# modular_pcb4.net
KiCad netlist of a schematic drawn in EAGLE
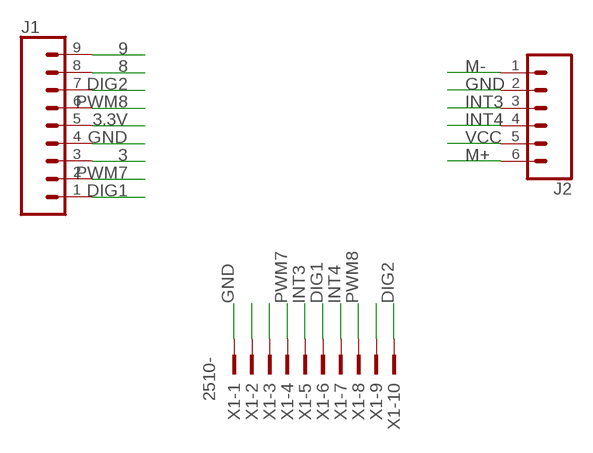
[diagram p0: schematic, sheet 1]

(export (version "E")
  (design (tool "Eeschema 10.0.6"))
  (components
    (comp (ref "J1")
      (value "CONN_09")
      (footprint "eagle-import:1X09")
      (libsource (lib "eagle-import") (part "CONN_09"))
    )
    (comp (ref "J2")
      (value "CONN_06FEMALE_LOCK")
      (footprint "eagle-import:1X06_FEMALE_LOCK.010")
      (libsource (lib "eagle-import") (part "CONN_06FEMALE_LOCK"))
    )
    (comp (ref "X1")
      (value "2510-")
      (footprint "eagle-import:PAK100_2500-10")
      (fields (field (name "MF") "3M") (field (name "MPN") "2510-6002UB"))
      (libsource (lib "eagle-import") (part "2510-"))
    )
  )
  (nets
    (net (code "1") (name "/3") (class "Default")
      (node (ref "J1") (pin "3") (pinfunction "3_3") (pintype "passive"))
    )
    (net (code "2") (name "/3.3V") (class "Default")
      (node (ref "J1") (pin "5") (pinfunction "5_5") (pintype "passive"))
    )
    (net (code "3") (name "/8") (class "Default")
      (node (ref "J1") (pin "8") (pinfunction "8_8") (pintype "passive"))
    )
    (net (code "4") (name "/9") (class "Default")
      (node (ref "J1") (pin "9") (pinfunction "9_9") (pintype "passive"))
    )
    (net (code "5") (name "/DIG1") (class "Default")
      (node (ref "J1") (pin "1") (pinfunction "1_1") (pintype "passive"))
      (node (ref "X1") (pin "6") (pinfunction "KL_6") (pintype "passive"))
    )
    (net (code "6") (name "/DIG2") (class "Default")
      (node (ref "J1") (pin "7") (pinfunction "7_7") (pintype "passive"))
      (node (ref "X1") (pin "10") (pinfunction "KL_10") (pintype "passive"))
    )
    (net (code "7") (name "/GND") (class "Default")
      (node (ref "J1") (pin "4") (pinfunction "4_4") (pintype "passive"))
      (node (ref "J2") (pin "2") (pinfunction "2_2") (pintype "passive"))
      (node (ref "X1") (pin "1") (pinfunction "KL_1") (pintype "passive"))
    )
    (net (code "8") (name "/INT3") (class "Default")
      (node (ref "J2") (pin "3") (pinfunction "3_3") (pintype "passive"))
      (node (ref "X1") (pin "5") (pinfunction "KL_5") (pintype "passive"))
    )
    (net (code "9") (name "/INT4") (class "Default")
      (node (ref "J2") (pin "4") (pinfunction "4_4") (pintype "passive"))
      (node (ref "X1") (pin "7") (pinfunction "KL_7") (pintype "passive"))
    )
    (net (code "10") (name "/M+") (class "Default")
      (node (ref "J2") (pin "6") (pinfunction "6_6") (pintype "passive"))
    )
    (net (code "11") (name "/M-") (class "Default")
      (node (ref "J2") (pin "1") (pinfunction "1_1") (pintype "passive"))
    )
    (net (code "12") (name "/PWM7") (class "Default")
      (node (ref "J1") (pin "2") (pinfunction "2_2") (pintype "passive"))
      (node (ref "X1") (pin "4") (pinfunction "KL_4") (pintype "passive"))
    )
    (net (code "13") (name "/PWM8") (class "Default")
      (node (ref "J1") (pin "6") (pinfunction "6_6") (pintype "passive"))
      (node (ref "X1") (pin "8") (pinfunction "KL_8") (pintype "passive"))
    )
    (net (code "14") (name "/VCC") (class "Default")
      (node (ref "J2") (pin "5") (pinfunction "5_5") (pintype "passive"))
      (node (ref "X1") (pin "9") (pinfunction "KL_9") (pintype "passive"))
    )
    (net (code "15") (name "unconnected-(X1C-KL-Pad2)") (class "Default")
      (node (ref "X1") (pin "2") (pinfunction "KL_2") (pintype "passive"))
    )
    (net (code "16") (name "unconnected-(X1D-KL-Pad3)") (class "Default")
      (node (ref "X1") (pin "3") (pinfunction "KL_3") (pintype "passive"))
    )
  )
)
